# DMM-8E-2.net
KiCad netlist of a schematic drawn in EAGLE
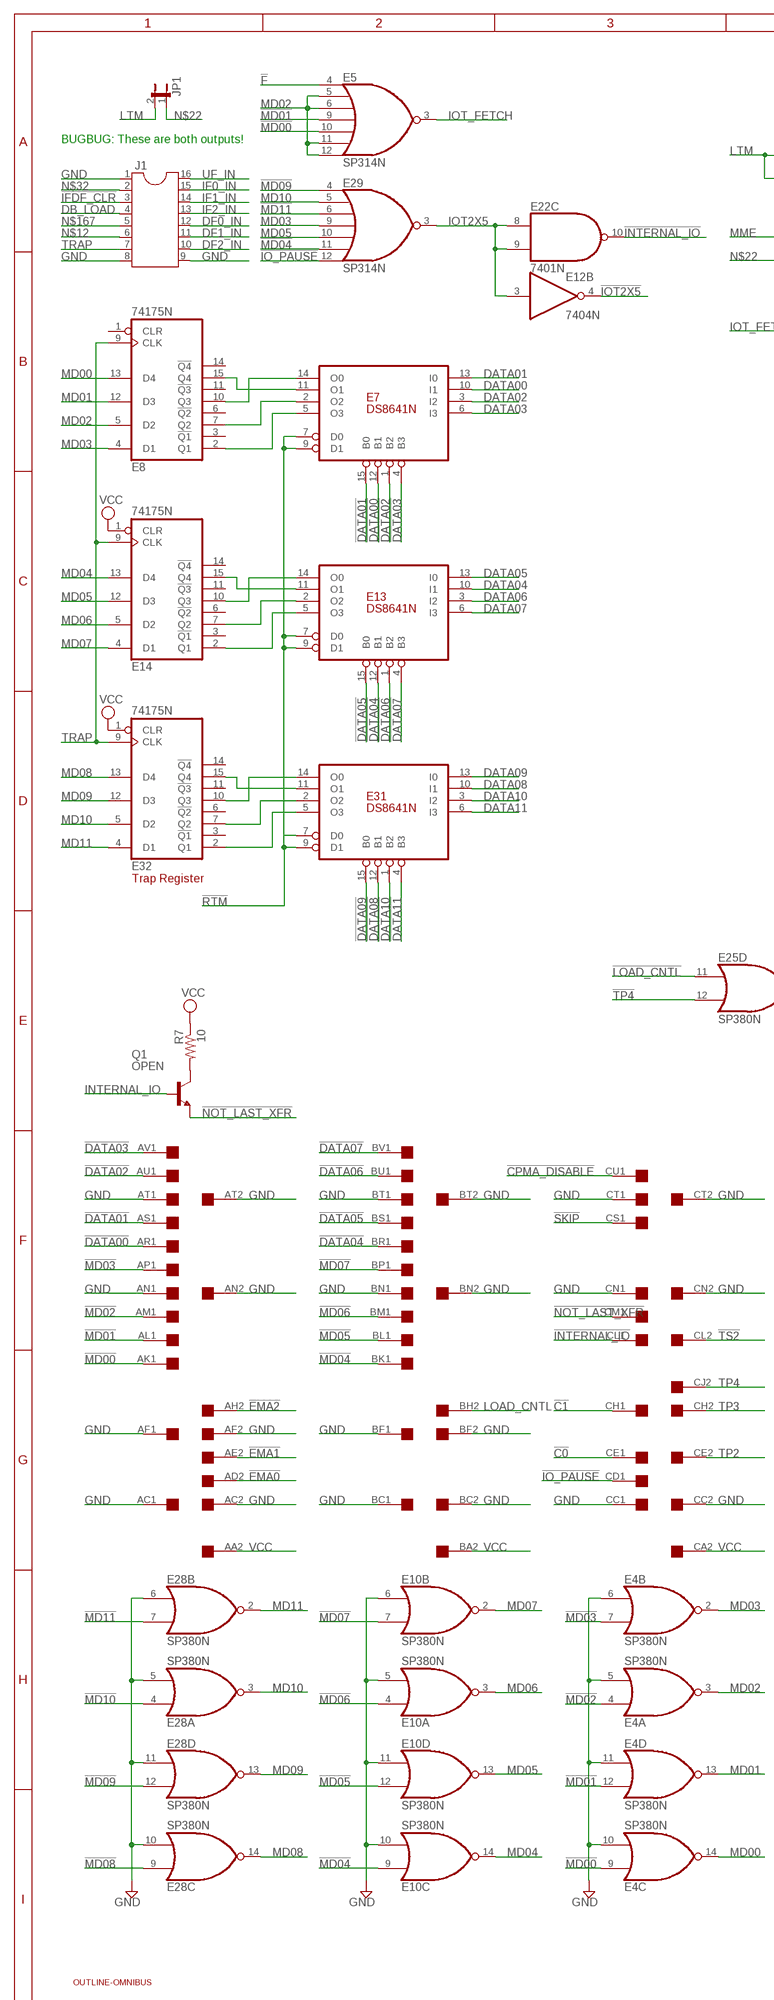
[diagram p0: schematic, sheet 1, part 1 of 2]
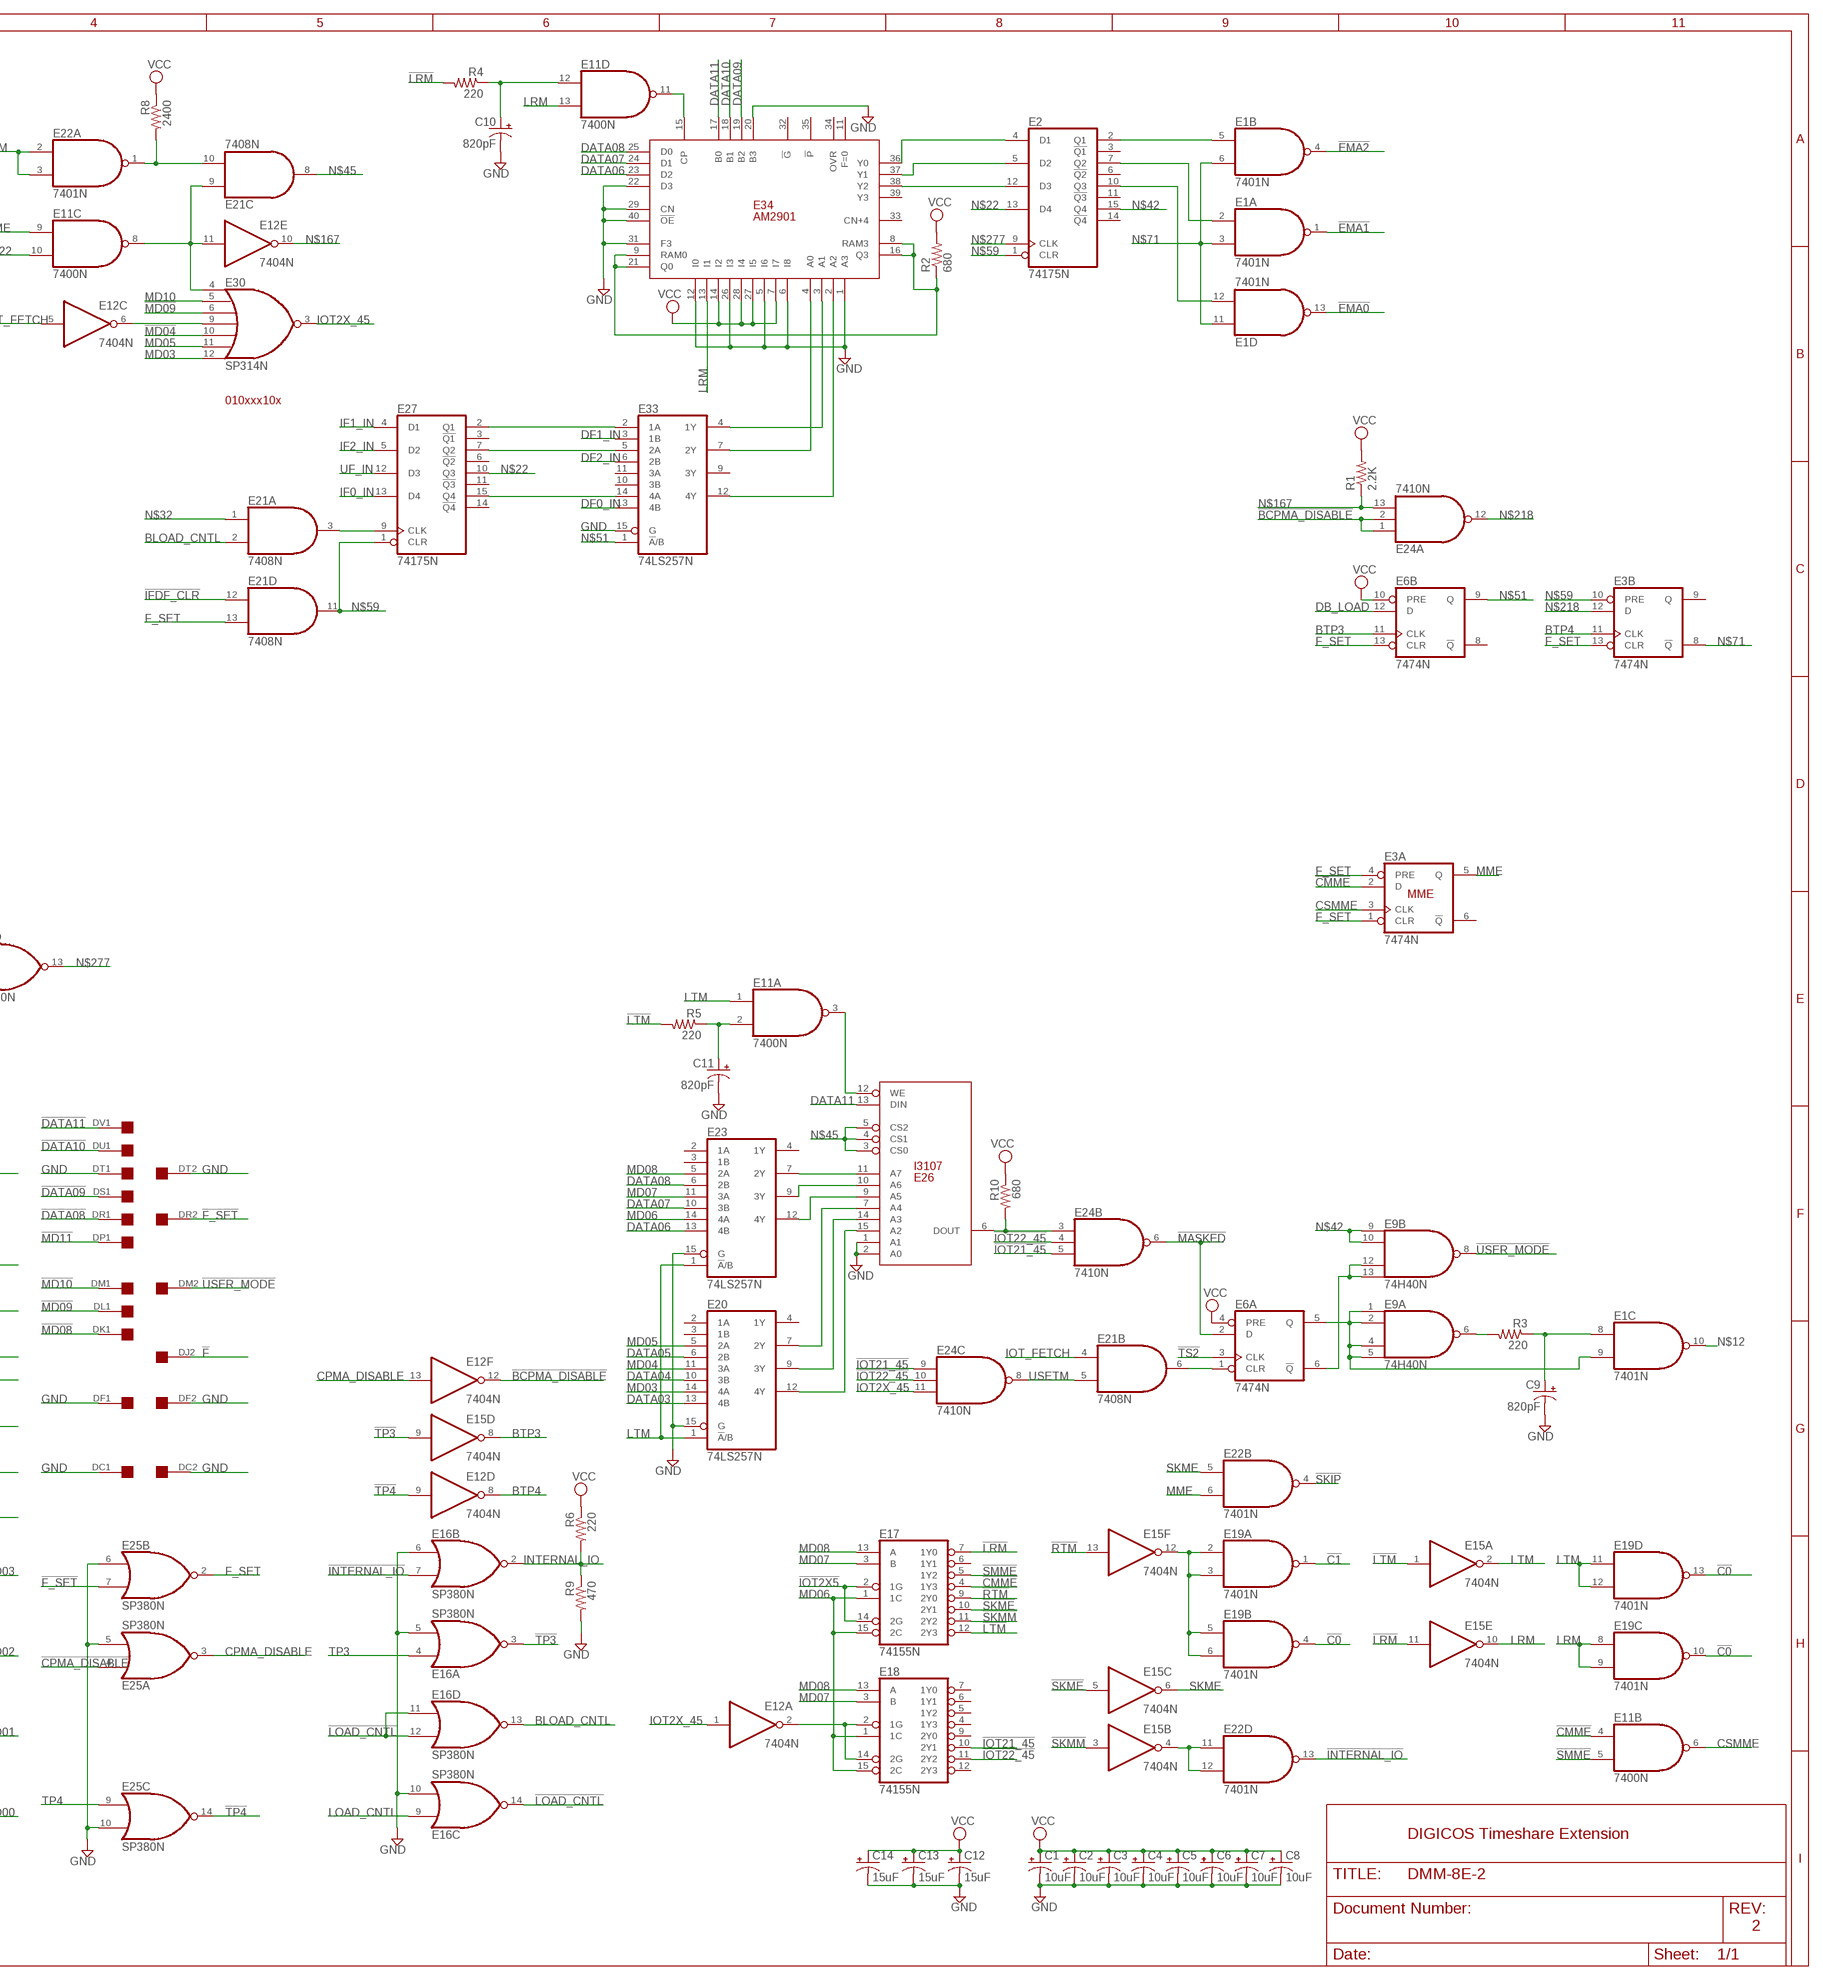
[diagram p1: schematic, sheet 1, part 2 of 2]

(export (version "E")
  (design (tool "Eeschema 10.0.6"))
  (components
    (comp (ref "C1")
      (value "10uF")
      (footprint "eagle-import:E15-5")
      (libsource (lib "eagle-import") (part "CPOL-USE15-5AXIAL"))
    )
    (comp (ref "C2")
      (value "10uF")
      (footprint "eagle-import:E15-5")
      (libsource (lib "eagle-import") (part "CPOL-USE15-5AXIAL"))
    )
    (comp (ref "C3")
      (value "10uF")
      (footprint "eagle-import:E15-5")
      (libsource (lib "eagle-import") (part "CPOL-USE15-5AXIAL"))
    )
    (comp (ref "C4")
      (value "10uF")
      (footprint "eagle-import:E15-5")
      (libsource (lib "eagle-import") (part "CPOL-USE15-5AXIAL"))
    )
    (comp (ref "C5")
      (value "10uF")
      (footprint "eagle-import:E15-5")
      (libsource (lib "eagle-import") (part "CPOL-USE15-5AXIAL"))
    )
    (comp (ref "C6")
      (value "10uF")
      (footprint "eagle-import:E15-5")
      (libsource (lib "eagle-import") (part "CPOL-USE15-5AXIAL"))
    )
    (comp (ref "C7")
      (value "10uF")
      (footprint "eagle-import:E15-5")
      (libsource (lib "eagle-import") (part "CPOL-USE15-5AXIAL"))
    )
    (comp (ref "C8")
      (value "10uF")
      (footprint "eagle-import:E15-5")
      (libsource (lib "eagle-import") (part "CPOL-USE15-5AXIAL"))
    )
    (comp (ref "C9")
      (value "820pF")
      (footprint "eagle-import:B45181C")
      (libsource (lib "eagle-import") (part "CPOL-USB45181C"))
    )
    (comp (ref "C10")
      (value "820pF")
      (footprint "eagle-import:B45181C")
      (libsource (lib "eagle-import") (part "CPOL-USB45181C"))
    )
    (comp (ref "C11")
      (value "820pF")
      (footprint "eagle-import:B45181C")
      (libsource (lib "eagle-import") (part "CPOL-USB45181C"))
    )
    (comp (ref "C12")
      (value "15uF")
      (footprint "eagle-import:TT5D7")
      (libsource (lib "eagle-import") (part "CPOL-USTT5D7"))
    )
    (comp (ref "C13")
      (value "15uF")
      (footprint "eagle-import:TT5D7")
      (libsource (lib "eagle-import") (part "CPOL-USTT5D7"))
    )
    (comp (ref "C14")
      (value "15uF")
      (footprint "eagle-import:TT5D7")
      (libsource (lib "eagle-import") (part "CPOL-USTT5D7"))
    )
    (comp (ref "E1")
      (value "7401N")
      (footprint "eagle-import:DIL14")
      (libsource (lib "eagle-import") (part "7401NLS"))
    )
    (comp (ref "E2")
      (value "74175N")
      (footprint "eagle-import:DIL16")
      (libsource (lib "eagle-import") (part "74175N"))
    )
    (comp (ref "E3")
      (value "7474N")
      (footprint "eagle-import:DIL14")
      (libsource (lib "eagle-import") (part "7474NLS"))
    )
    (comp (ref "E4")
      (value "SP380N")
      (footprint "eagle-import:DIL14")
      (libsource (lib "eagle-import") (part "SP380N"))
    )
    (comp (ref "E5")
      (value "SP314N")
      (footprint "eagle-import:DIL14")
      (libsource (lib "eagle-import") (part "SP314N"))
    )
    (comp (ref "E6")
      (value "7474N")
      (footprint "eagle-import:DIL14")
      (libsource (lib "eagle-import") (part "7474NLS"))
    )
    (comp (ref "E7")
      (value "DS8641N")
      (footprint "eagle-import:DIL16")
      (libsource (lib "eagle-import") (part "DS8641N"))
    )
    (comp (ref "E8")
      (value "74175N")
      (footprint "eagle-import:DIL16")
      (libsource (lib "eagle-import") (part "74175N"))
    )
    (comp (ref "E9")
      (value "74H40N")
      (footprint "eagle-import:DIL14")
      (libsource (lib "eagle-import") (part "7440N"))
    )
    (comp (ref "E10")
      (value "SP380N")
      (footprint "eagle-import:DIL14")
      (libsource (lib "eagle-import") (part "SP380N"))
    )
    (comp (ref "E11")
      (value "7400N")
      (footprint "eagle-import:DIL14")
      (libsource (lib "eagle-import") (part "7400N"))
    )
    (comp (ref "E12")
      (value "7404N")
      (footprint "eagle-import:DIL14")
      (libsource (lib "eagle-import") (part "7404N"))
    )
    (comp (ref "E13")
      (value "DS8641N")
      (footprint "eagle-import:DIL16")
      (libsource (lib "eagle-import") (part "DS8641N"))
    )
    (comp (ref "E14")
      (value "74175N")
      (footprint "eagle-import:DIL16")
      (libsource (lib "eagle-import") (part "74175N"))
    )
    (comp (ref "E15")
      (value "7404N")
      (footprint "eagle-import:DIL14")
      (libsource (lib "eagle-import") (part "7404N"))
    )
    (comp (ref "E16")
      (value "SP380N")
      (footprint "eagle-import:DIL14")
      (libsource (lib "eagle-import") (part "SP380N"))
    )
    (comp (ref "E17")
      (value "74155N")
      (footprint "eagle-import:DIL16")
      (libsource (lib "eagle-import") (part "74155N"))
    )
    (comp (ref "E18")
      (value "74155N")
      (footprint "eagle-import:DIL16")
      (libsource (lib "eagle-import") (part "74155N"))
    )
    (comp (ref "E19")
      (value "7401N")
      (footprint "eagle-import:DIL14")
      (libsource (lib "eagle-import") (part "7401NLS"))
    )
    (comp (ref "E20")
      (value "74LS257N")
      (footprint "eagle-import:DIL16")
      (libsource (lib "eagle-import") (part "74257NLS"))
    )
    (comp (ref "E21")
      (value "7408N")
      (footprint "eagle-import:DIL14")
      (libsource (lib "eagle-import") (part "7408NLS"))
    )
    (comp (ref "E22")
      (value "7401N")
      (footprint "eagle-import:DIL14")
      (libsource (lib "eagle-import") (part "7401NLS"))
    )
    (comp (ref "E23")
      (value "74LS257N")
      (footprint "eagle-import:DIL16")
      (libsource (lib "eagle-import") (part "74257NLS"))
    )
    (comp (ref "E24")
      (value "7410N")
      (footprint "eagle-import:DIL14")
      (libsource (lib "eagle-import") (part "7410N"))
    )
    (comp (ref "E25")
      (value "SP380N")
      (footprint "eagle-import:DIL14")
      (libsource (lib "eagle-import") (part "SP380N"))
    )
    (comp (ref "E26")
      (value "I3107")
      (footprint "eagle-import:DIL16")
      (libsource (lib "eagle-import") (part "I3107"))
    )
    (comp (ref "E27")
      (value "74175N")
      (footprint "eagle-import:DIL16")
      (libsource (lib "eagle-import") (part "74175N"))
    )
    (comp (ref "E28")
      (value "SP380N")
      (footprint "eagle-import:DIL14")
      (libsource (lib "eagle-import") (part "SP380N"))
    )
    (comp (ref "E29")
      (value "SP314N")
      (footprint "eagle-import:DIL14")
      (libsource (lib "eagle-import") (part "SP314N"))
    )
    (comp (ref "E30")
      (value "SP314N")
      (footprint "eagle-import:DIL14")
      (libsource (lib "eagle-import") (part "SP314N"))
    )
    (comp (ref "E31")
      (value "DS8641N")
      (footprint "eagle-import:DIL16")
      (libsource (lib "eagle-import") (part "DS8641N"))
    )
    (comp (ref "E32")
      (value "74175N")
      (footprint "eagle-import:DIL16")
      (libsource (lib "eagle-import") (part "74175N"))
    )
    (comp (ref "E33")
      (value "74LS257N")
      (footprint "eagle-import:DIL16")
      (libsource (lib "eagle-import") (part "74257NLS"))
    )
    (comp (ref "E34")
      (value "AM2901")
      (footprint "eagle-import:DIL40")
      (libsource (lib "eagle-import") (part "AM2901"))
    )
    (comp (ref "J1")
      (value "DIL16S")
      (footprint "eagle-import:SOCKET-16")
      (libsource (lib "eagle-import") (part "DIL16S"))
    )
    (comp (ref "JP1")
      (value "JP1E")
      (footprint "eagle-import:JP1")
      (libsource (lib "eagle-import") (part "JP1E"))
    )
    (comp (ref "Q1")
      (value "OPEN")
      (footprint "eagle-import:TO5")
      (libsource (lib "eagle-import") (part "-NPN-TO5"))
    )
    (comp (ref "R1")
      (value "2.2K")
      (footprint "eagle-import:0207_10")
      (libsource (lib "eagle-import") (part "R-US_0207/10"))
    )
    (comp (ref "R2")
      (value "680")
      (footprint "eagle-import:0207_10")
      (libsource (lib "eagle-import") (part "R-US_0207/10"))
    )
    (comp (ref "R3")
      (value "220")
      (footprint "eagle-import:0207_10")
      (libsource (lib "eagle-import") (part "R-US_0207/10"))
    )
    (comp (ref "R4")
      (value "220")
      (footprint "eagle-import:0207_10")
      (libsource (lib "eagle-import") (part "R-US_0207/10"))
    )
    (comp (ref "R5")
      (value "220")
      (footprint "eagle-import:0207_10")
      (libsource (lib "eagle-import") (part "R-US_0207/10"))
    )
    (comp (ref "R6")
      (value "220")
      (footprint "eagle-import:0207_10")
      (libsource (lib "eagle-import") (part "R-US_0207/10"))
    )
    (comp (ref "R7")
      (value "10")
      (footprint "eagle-import:0207_10")
      (libsource (lib "eagle-import") (part "R-US_0207/10"))
    )
    (comp (ref "R8")
      (value "2400")
      (footprint "eagle-import:0207_10")
      (libsource (lib "eagle-import") (part "R-US_0207/10"))
    )
    (comp (ref "R9")
      (value "470")
      (footprint "eagle-import:0207_10")
      (libsource (lib "eagle-import") (part "R-US_0207/10"))
    )
    (comp (ref "R10")
      (value "680")
      (footprint "eagle-import:0207_10")
      (libsource (lib "eagle-import") (part "R-US_0207/10"))
    )
    (comp (ref "U$1")
      (value "OUTLINE-OMNIBUS")
      (footprint "eagle-import:OMNIBUS")
      (libsource (lib "eagle-import") (part "OUTLINE-OMNIBUS"))
    )
    (comp (ref "U$2")
      (value "QUAD")
      (footprint "eagle-import:EDGE-CON8")
      (libsource (lib "eagle-import") (part "QUAD"))
    )
  )
  (nets
    (net (code "1") (name "/BLOAD_CNTL") (class "Default")
      (node (ref "E16") (pin "13") (pinfunction "O_13") (pintype "output"))
      (node (ref "E21") (pin "2") (pinfunction "I1_2") (pintype "input"))
    )
    (net (code "2") (name "/BTP3") (class "Default")
      (node (ref "E15") (pin "8") (pinfunction "O_8") (pintype "output"))
      (node (ref "E6") (pin "11") (pinfunction "CLK_11") (pintype "input"))
    )
    (net (code "3") (name "/BTP4") (class "Default")
      (node (ref "E12") (pin "8") (pinfunction "O_8") (pintype "output"))
      (node (ref "E3") (pin "11") (pinfunction "CLK_11") (pintype "input"))
    )
    (net (code "4") (name "/CPMA_DISABLE") (class "Default")
      (node (ref "E12") (pin "13") (pinfunction "I_13") (pintype "input"))
      (node (ref "E25") (pin "3") (pinfunction "O_3") (pintype "output"))
    )
    (net (code "5") (name "/CSMME") (class "Default")
      (node (ref "E11") (pin "6") (pinfunction "O_6") (pintype "output"))
      (node (ref "E3") (pin "3") (pinfunction "CLK_3") (pintype "input"))
    )
    (net (code "6") (name "/DATA00") (class "Default")
      (node (ref "E7") (pin "10") (pinfunction "I1_10") (pintype "output"))
    )
    (net (code "7") (name "/DATA01") (class "Default")
      (node (ref "E7") (pin "13") (pinfunction "I0_13") (pintype "output"))
    )
    (net (code "8") (name "/DATA02") (class "Default")
      (node (ref "E7") (pin "3") (pinfunction "I2_3") (pintype "output"))
    )
    (net (code "9") (name "/DATA03") (class "Default")
      (node (ref "E20") (pin "13") (pinfunction "4B_13") (pintype "input"))
      (node (ref "E7") (pin "6") (pinfunction "I3_6") (pintype "output"))
    )
    (net (code "10") (name "/DATA04") (class "Default")
      (node (ref "E13") (pin "10") (pinfunction "I1_10") (pintype "output"))
      (node (ref "E20") (pin "10") (pinfunction "3B_10") (pintype "input"))
    )
    (net (code "11") (name "/DATA05") (class "Default")
      (node (ref "E13") (pin "13") (pinfunction "I0_13") (pintype "output"))
      (node (ref "E20") (pin "6") (pinfunction "2B_6") (pintype "input"))
    )
    (net (code "12") (name "/DATA06") (class "Default")
      (node (ref "E13") (pin "3") (pinfunction "I2_3") (pintype "output"))
      (node (ref "E23") (pin "13") (pinfunction "4B_13") (pintype "input"))
      (node (ref "E34") (pin "23") (pinfunction "D2_23") (pintype "input"))
    )
    (net (code "13") (name "/DATA07") (class "Default")
      (node (ref "E13") (pin "6") (pinfunction "I3_6") (pintype "output"))
      (node (ref "E23") (pin "10") (pinfunction "3B_10") (pintype "input"))
      (node (ref "E34") (pin "24") (pinfunction "D1_24") (pintype "input"))
    )
    (net (code "14") (name "/DATA08") (class "Default")
      (node (ref "E23") (pin "6") (pinfunction "2B_6") (pintype "input"))
      (node (ref "E31") (pin "10") (pinfunction "I1_10") (pintype "output"))
      (node (ref "E34") (pin "25") (pinfunction "D0_25") (pintype "input"))
    )
    (net (code "15") (name "/DATA09") (class "Default")
      (node (ref "E31") (pin "13") (pinfunction "I0_13") (pintype "output"))
      (node (ref "E34") (pin "19") (pinfunction "B2_19") (pintype "input"))
    )
    (net (code "16") (name "/DATA10") (class "Default")
      (node (ref "E31") (pin "3") (pinfunction "I2_3") (pintype "output"))
      (node (ref "E34") (pin "18") (pinfunction "B1_18") (pintype "input"))
    )
    (net (code "17") (name "/DATA11") (class "Default")
      (node (ref "E26") (pin "13") (pinfunction "DIN_13") (pintype "input"))
      (node (ref "E31") (pin "6") (pinfunction "I3_6") (pintype "output"))
      (node (ref "E34") (pin "17") (pinfunction "B0_17") (pintype "input"))
    )
    (net (code "18") (name "/DB_LOAD") (class "Default")
      (node (ref "E6") (pin "12") (pinfunction "D_12") (pintype "input"))
      (node (ref "J1") (pin "4") (pinfunction "4_4") (pintype "passive"))
    )
    (net (code "19") (name "/DF0_IN") (class "Default")
      (node (ref "E33") (pin "13") (pinfunction "4B_13") (pintype "input"))
      (node (ref "J1") (pin "12") (pinfunction "12_12") (pintype "passive"))
    )
    (net (code "20") (name "/DF1_IN") (class "Default")
      (node (ref "E33") (pin "3") (pinfunction "1B_3") (pintype "input"))
      (node (ref "J1") (pin "11") (pinfunction "11_11") (pintype "passive"))
    )
    (net (code "21") (name "/DF2_IN") (class "Default")
      (node (ref "E33") (pin "6") (pinfunction "2B_6") (pintype "input"))
      (node (ref "J1") (pin "10") (pinfunction "10_10") (pintype "passive"))
    )
    (net (code "22") (name "/F_SET") (class "Default")
      (node (ref "E21") (pin "13") (pinfunction "I1_13") (pintype "input"))
      (node (ref "E25") (pin "2") (pinfunction "O_2") (pintype "output"))
      (node (ref "E3") (pin "1") (pinfunction "CLR_1") (pintype "input"))
      (node (ref "E3") (pin "13") (pinfunction "CLR_13") (pintype "input"))
      (node (ref "E3") (pin "4") (pinfunction "PRE_4") (pintype "input"))
      (node (ref "E6") (pin "13") (pinfunction "CLR_13") (pintype "input"))
    )
    (net (code "23") (name "/IF0_IN") (class "Default")
      (node (ref "E27") (pin "13") (pinfunction "D4_13") (pintype "input"))
      (node (ref "J1") (pin "15") (pinfunction "15_15") (pintype "passive"))
    )
    (net (code "24") (name "/IF1_IN") (class "Default")
      (node (ref "E27") (pin "4") (pinfunction "D1_4") (pintype "input"))
      (node (ref "J1") (pin "14") (pinfunction "14_14") (pintype "passive"))
    )
    (net (code "25") (name "/IF2_IN") (class "Default")
      (node (ref "E27") (pin "5") (pinfunction "D2_5") (pintype "input"))
      (node (ref "J1") (pin "13") (pinfunction "13_13") (pintype "passive"))
    )
    (net (code "26") (name "/INTERNAL_IO") (class "Default")
      (node (ref "E16") (pin "2") (pinfunction "O_2") (pintype "output"))
      (node (ref "Q1") (pin "2") (pinfunction "B_2") (pintype "passive"))
      (node (ref "R6") (pin "2") (pinfunction "2_2") (pintype "passive"))
      (node (ref "R9") (pin "1") (pinfunction "1_1") (pintype "passive"))
    )
    (net (code "27") (name "/IOT2X5") (class "Default")
      (node (ref "E12") (pin "3") (pinfunction "I_3") (pintype "input"))
      (node (ref "E22") (pin "8") (pinfunction "I0_8") (pintype "input"))
      (node (ref "E22") (pin "9") (pinfunction "I1_9") (pintype "input"))
      (node (ref "E29") (pin "3") (pinfunction "O_3") (pintype "output"))
    )
    (net (code "28") (name "/IOT2X_45") (class "Default")
      (node (ref "E12") (pin "1") (pinfunction "I_1") (pintype "input"))
      (node (ref "E24") (pin "11") (pinfunction "I2_11") (pintype "input"))
      (node (ref "E30") (pin "3") (pinfunction "O_3") (pintype "output"))
    )
    (net (code "29") (name "/IOT_FETCH") (class "Default")
      (node (ref "E12") (pin "5") (pinfunction "I_5") (pintype "input"))
      (node (ref "E21") (pin "4") (pinfunction "I0_4") (pintype "input"))
      (node (ref "E5") (pin "3") (pinfunction "O_3") (pintype "output"))
    )
    (net (code "30") (name "/LOAD_CNTL") (class "Default")
      (node (ref "E16") (pin "9") (pinfunction "I0_9") (pintype "input"))
      (node (ref "U$2") (pin "BH2") (pinfunction "1_BH2") (pintype "bidirectional"))
    )
    (net (code "31") (name "/LRM") (class "Default")
      (node (ref "E11") (pin "13") (pinfunction "I1_13") (pintype "input"))
      (node (ref "E15") (pin "10") (pinfunction "O_10") (pintype "output"))
      (node (ref "E19") (pin "8") (pinfunction "I0_8") (pintype "input"))
      (node (ref "E19") (pin "9") (pinfunction "I1_9") (pintype "input"))
      (node (ref "E34") (pin "13") (pinfunction "I1_13") (pintype "input"))
    )
    (net (code "32") (name "/LTM") (class "Default")
      (node (ref "E11") (pin "1") (pinfunction "I0_1") (pintype "input"))
      (node (ref "E15") (pin "2") (pinfunction "O_2") (pintype "output"))
      (node (ref "E19") (pin "11") (pinfunction "I0_11") (pintype "input"))
      (node (ref "E19") (pin "12") (pinfunction "I1_12") (pintype "input"))
      (node (ref "E20") (pin "1") (pinfunction "~{A}/B_1") (pintype "input"))
      (node (ref "E22") (pin "2") (pinfunction "I0_2") (pintype "input"))
      (node (ref "E22") (pin "3") (pinfunction "I1_3") (pintype "input"))
      (node (ref "E23") (pin "1") (pinfunction "~{A}/B_1") (pintype "input"))
      (node (ref "JP1") (pin "2") (pinfunction "2_2") (pintype "passive"))
    )
    (net (code "33") (name "/MD00") (class "Default")
      (node (ref "E4") (pin "14") (pinfunction "O_14") (pintype "output"))
      (node (ref "E8") (pin "13") (pinfunction "D4_13") (pintype "input"))
    )
    (net (code "34") (name "/MD01") (class "Default")
      (node (ref "E4") (pin "13") (pinfunction "O_13") (pintype "output"))
      (node (ref "E8") (pin "12") (pinfunction "D3_12") (pintype "input"))
    )
    (net (code "35") (name "/MD02") (class "Default")
      (node (ref "E4") (pin "3") (pinfunction "O_3") (pintype "output"))
      (node (ref "E5") (pin "11") (pinfunction "I5_11") (pintype "input"))
      (node (ref "E5") (pin "12") (pinfunction "I6_12") (pintype "input"))
      (node (ref "E5") (pin "5") (pinfunction "I1_5") (pintype "input"))
      (node (ref "E5") (pin "6") (pinfunction "I2_6") (pintype "input"))
      (node (ref "E8") (pin "5") (pinfunction "D2_5") (pintype "input"))
    )
    (net (code "36") (name "/MD03") (class "Default")
      (node (ref "E20") (pin "14") (pinfunction "4A_14") (pintype "input"))
      (node (ref "E29") (pin "9") (pinfunction "I3_9") (pintype "input"))
      (node (ref "E30") (pin "12") (pinfunction "I6_12") (pintype "input"))
      (node (ref "E4") (pin "2") (pinfunction "O_2") (pintype "output"))
      (node (ref "E8") (pin "4") (pinfunction "D1_4") (pintype "input"))
    )
    (net (code "37") (name "/MD04") (class "Default")
      (node (ref "E10") (pin "14") (pinfunction "O_14") (pintype "output"))
      (node (ref "E14") (pin "13") (pinfunction "D4_13") (pintype "input"))
      (node (ref "E20") (pin "11") (pinfunction "3A_11") (pintype "input"))
    )
    (net (code "38") (name "/MD05") (class "Default")
      (node (ref "E10") (pin "13") (pinfunction "O_13") (pintype "output"))
      (node (ref "E14") (pin "12") (pinfunction "D3_12") (pintype "input"))
      (node (ref "E20") (pin "5") (pinfunction "2A_5") (pintype "input"))
      (node (ref "E29") (pin "10") (pinfunction "I4_10") (pintype "input"))
      (node (ref "E30") (pin "11") (pinfunction "I5_11") (pintype "input"))
    )
    (net (code "39") (name "/MD06") (class "Default")
      (node (ref "E10") (pin "3") (pinfunction "O_3") (pintype "output"))
      (node (ref "E14") (pin "5") (pinfunction "D2_5") (pintype "input"))
      (node (ref "E17") (pin "1") (pinfunction "1C_1") (pintype "input"))
      (node (ref "E17") (pin "15") (pinfunction "2C_15") (pintype "input"))
      (node (ref "E18") (pin "1") (pinfunction "1C_1") (pintype "input"))
      (node (ref "E18") (pin "15") (pinfunction "2C_15") (pintype "input"))
      (node (ref "E23") (pin "14") (pinfunction "4A_14") (pintype "input"))
    )
    (net (code "40") (name "/MD07") (class "Default")
      (node (ref "E10") (pin "2") (pinfunction "O_2") (pintype "output"))
      (node (ref "E14") (pin "4") (pinfunction "D1_4") (pintype "input"))
      (node (ref "E17") (pin "3") (pinfunction "B_3") (pintype "input"))
      (node (ref "E18") (pin "3") (pinfunction "B_3") (pintype "input"))
      (node (ref "E23") (pin "11") (pinfunction "3A_11") (pintype "input"))
    )
    (net (code "41") (name "/MD08") (class "Default")
      (node (ref "E17") (pin "13") (pinfunction "A_13") (pintype "input"))
      (node (ref "E18") (pin "13") (pinfunction "A_13") (pintype "input"))
      (node (ref "E23") (pin "5") (pinfunction "2A_5") (pintype "input"))
      (node (ref "E28") (pin "14") (pinfunction "O_14") (pintype "output"))
      (node (ref "E32") (pin "13") (pinfunction "D4_13") (pintype "input"))
    )
    (net (code "42") (name "/MD09") (class "Default")
      (node (ref "E28") (pin "13") (pinfunction "O_13") (pintype "output"))
      (node (ref "E32") (pin "12") (pinfunction "D3_12") (pintype "input"))
    )
    (net (code "43") (name "/MD10") (class "Default")
      (node (ref "E28") (pin "3") (pinfunction "O_3") (pintype "output"))
      (node (ref "E29") (pin "5") (pinfunction "I1_5") (pintype "input"))
      (node (ref "E30") (pin "5") (pinfunction "I1_5") (pintype "input"))
      (node (ref "E32") (pin "5") (pinfunction "D2_5") (pintype "input"))
    )
    (net (code "44") (name "/MD11") (class "Default")
      (node (ref "E28") (pin "2") (pinfunction "O_2") (pintype "output"))
      (node (ref "E32") (pin "4") (pinfunction "D1_4") (pintype "input"))
    )
    (net (code "45") (name "/MME") (class "Default")
      (node (ref "E11") (pin "9") (pinfunction "I0_9") (pintype "input"))
      (node (ref "E22") (pin "6") (pinfunction "I1_6") (pintype "input"))
      (node (ref "E3") (pin "5") (pinfunction "Q_5") (pintype "output"))
    )
    (net (code "46") (name "/N$12") (class "Default")
      (node (ref "E1") (pin "10") (pinfunction "O_10") (pintype "open_collector"))
      (node (ref "J1") (pin "6") (pinfunction "6_6") (pintype "passive"))
    )
    (net (code "47") (name "/N$22") (class "Default")
      (node (ref "E11") (pin "10") (pinfunction "I1_10") (pintype "input"))
      (node (ref "E2") (pin "13") (pinfunction "D4_13") (pintype "input"))
      (node (ref "E27") (pin "10") (pinfunction "Q3_10") (pintype "output"))
      (node (ref "JP1") (pin "1") (pinfunction "1_1") (pintype "passive"))
    )
    (net (code "48") (name "/N$32") (class "Default")
      (node (ref "E21") (pin "1") (pinfunction "I0_1") (pintype "input"))
      (node (ref "J1") (pin "2") (pinfunction "2_2") (pintype "passive"))
    )
    (net (code "49") (name "/N$42") (class "Default")
      (node (ref "E2") (pin "15") (pinfunction "Q4_15") (pintype "output"))
      (node (ref "E9") (pin "10") (pinfunction "I1_10") (pintype "input"))
      (node (ref "E9") (pin "9") (pinfunction "I0_9") (pintype "input"))
    )
    (net (code "50") (name "/N$45") (class "Default")
      (node (ref "E21") (pin "8") (pinfunction "O_8") (pintype "output"))
      (node (ref "E26") (pin "3") (pinfunction "CS0_3") (pintype "input"))
      (node (ref "E26") (pin "4") (pinfunction "CS1_4") (pintype "input"))
      (node (ref "E26") (pin "5") (pinfunction "CS2_5") (pintype "input"))
    )
    (net (code "51") (name "/N$51") (class "Default")
      (node (ref "E33") (pin "1") (pinfunction "~{A}/B_1") (pintype "input"))
      (node (ref "E6") (pin "9") (pinfunction "Q_9") (pintype "output"))
    )
    (net (code "52") (name "/N$59") (class "Default")
      (node (ref "E2") (pin "1") (pinfunction "CLR_1") (pintype "input"))
      (node (ref "E21") (pin "11") (pinfunction "O_11") (pintype "output"))
      (node (ref "E27") (pin "1") (pinfunction "CLR_1") (pintype "input"))
      (node (ref "E3") (pin "10") (pinfunction "PRE_10") (pintype "input"))
    )
    (net (code "53") (name "/N$71") (class "Default")
      (node (ref "E1") (pin "11") (pinfunction "I0_11") (pintype "input"))
      (node (ref "E1") (pin "3") (pinfunction "I1_3") (pintype "input"))
      (node (ref "E1") (pin "6") (pinfunction "I1_6") (pintype "input"))
      (node (ref "E3") (pin "8") (pinfunction "~{Q}_8") (pintype "output"))
    )
    (net (code "54") (name "/N$167") (class "Default")
      (node (ref "E12") (pin "10") (pinfunction "O_10") (pintype "output"))
      (node (ref "E24") (pin "13") (pinfunction "I2_13") (pintype "input"))
      (node (ref "J1") (pin "5") (pinfunction "5_5") (pintype "passive"))
      (node (ref "R1") (pin "1") (pinfunction "1_1") (pintype "passive"))
    )
    (net (code "55") (name "/N$218") (class "Default")
      (node (ref "E24") (pin "12") (pinfunction "O_12") (pintype "output"))
      (node (ref "E3") (pin "12") (pinfunction "D_12") (pintype "input"))
    )
    (net (code "56") (name "/N$277") (class "Default")
      (node (ref "E2") (pin "9") (pinfunction "CLK_9") (pintype "input"))
      (node (ref "E25") (pin "13") (pinfunction "O_13") (pintype "output"))
    )
    (net (code "57") (name "/SKME") (class "Default")
      (node (ref "E15") (pin "6") (pinfunction "O_6") (pintype "output"))
      (node (ref "E22") (pin "5") (pinfunction "I0_5") (pintype "input"))
    )
    (net (code "58") (name "/TP2") (class "Default")
      (node (ref "U$2") (pin "CE2") (pinfunction "1_CE2") (pintype "bidirectional"))
    )
    (net (code "59") (name "/TP3") (class "Default")
      (node (ref "E16") (pin "4") (pinfunction "I0_4") (pintype "input"))
      (node (ref "U$2") (pin "CH2") (pinfunction "1_CH2") (pintype "bidirectional"))
    )
    (net (code "60") (name "/TP4") (class "Default")
      (node (ref "E25") (pin "9") (pinfunction "I0_9") (pintype "input"))
      (node (ref "U$2") (pin "CJ2") (pinfunction "1_CJ2") (pintype "bidirectional"))
    )
    (net (code "61") (name "/TRAP") (class "Default")
      (node (ref "E14") (pin "9") (pinfunction "CLK_9") (pintype "input"))
      (node (ref "E32") (pin "9") (pinfunction "CLK_9") (pintype "input"))
      (node (ref "E8") (pin "9") (pinfunction "CLK_9") (pintype "input"))
      (node (ref "J1") (pin "7") (pinfunction "7_7") (pintype "passive"))
    )
    (net (code "62") (name "/UF_IN") (class "Default")
      (node (ref "E27") (pin "12") (pinfunction "D3_12") (pintype "input"))
      (node (ref "J1") (pin "16") (pinfunction "16_16") (pintype "passive"))
    )
    (net (code "63") (name "/USETM") (class "Default")
      (node (ref "E21") (pin "5") (pinfunction "I1_5") (pintype "input"))
      (node (ref "E24") (pin "8") (pinfunction "O_8") (pintype "output"))
    )
    (net (code "64") (name "/~{BCPMA_DISABLE}") (class "Default")
      (node (ref "E12") (pin "12") (pinfunction "O_12") (pintype "output"))
      (node (ref "E24") (pin "1") (pinfunction "I0_1") (pintype "input"))
      (node (ref "E24") (pin "2") (pinfunction "I1_2") (pintype "input"))
    )
    (net (code "65") (name "/~{C0}") (class "Default")
      (node (ref "E19") (pin "10") (pinfunction "O_10") (pintype "open_collector"))
      (node (ref "E19") (pin "13") (pinfunction "O_13") (pintype "open_collector"))
      (node (ref "E19") (pin "4") (pinfunction "O_4") (pintype "open_collector"))
      (node (ref "U$2") (pin "CE1") (pinfunction "1_CE1") (pintype "bidirectional"))
    )
    (net (code "66") (name "/~{C1}") (class "Default")
      (node (ref "E19") (pin "1") (pinfunction "O_1") (pintype "open_collector"))
      (node (ref "U$2") (pin "CH1") (pinfunction "1_CH1") (pintype "bidirectional"))
    )
    (net (code "67") (name "/~{CMME}") (class "Default")
      (node (ref "E11") (pin "4") (pinfunction "I0_4") (pintype "input"))
      (node (ref "E17") (pin "4") (pinfunction "1Y3_4") (pintype "output"))
      (node (ref "E3") (pin "2") (pinfunction "D_2") (pintype "input"))
    )
    (net (code "68") (name "/~{CPMA_DISABLE}") (class "Default")
      (node (ref "E25") (pin "4") (pinfunction "I0_4") (pintype "input"))
      (node (ref "U$2") (pin "CU1") (pinfunction "1_CU1") (pintype "bidirectional"))
    )
    (net (code "69") (name "/~{DATA00}") (class "Default")
      (node (ref "E7") (pin "12") (pinfunction "B1_12") (pintype "bidirectional"))
      (node (ref "U$2") (pin "AR1") (pinfunction "1_AR1") (pintype "bidirectional"))
    )
    (net (code "70") (name "/~{DATA01}") (class "Default")
      (node (ref "E7") (pin "15") (pinfunction "B0_15") (pintype "bidirectional"))
      (node (ref "U$2") (pin "AS1") (pinfunction "1_AS1") (pintype "bidirectional"))
    )
    (net (code "71") (name "/~{DATA02}") (class "Default")
      (node (ref "E7") (pin "1") (pinfunction "B2_1") (pintype "bidirectional"))
      (node (ref "U$2") (pin "AU1") (pinfunction "1_AU1") (pintype "bidirectional"))
    )
    (net (code "72") (name "/~{DATA03}") (class "Default")
      (node (ref "E7") (pin "4") (pinfunction "B3_4") (pintype "bidirectional"))
      (node (ref "U$2") (pin "AV1") (pinfunction "1_AV1") (pintype "bidirectional"))
    )
    (net (code "73") (name "/~{DATA04}") (class "Default")
      (node (ref "E13") (pin "12") (pinfunction "B1_12") (pintype "bidirectional"))
      (node (ref "U$2") (pin "BR1") (pinfunction "1_BR1") (pintype "bidirectional"))
    )
    (net (code "74") (name "/~{DATA05}") (class "Default")
      (node (ref "E13") (pin "15") (pinfunction "B0_15") (pintype "bidirectional"))
      (node (ref "U$2") (pin "BS1") (pinfunction "1_BS1") (pintype "bidirectional"))
    )
    (net (code "75") (name "/~{DATA06}") (class "Default")
      (node (ref "E13") (pin "1") (pinfunction "B2_1") (pintype "bidirectional"))
      (node (ref "U$2") (pin "BU1") (pinfunction "1_BU1") (pintype "bidirectional"))
    )
    (net (code "76") (name "/~{DATA07}") (class "Default")
      (node (ref "E13") (pin "4") (pinfunction "B3_4") (pintype "bidirectional"))
      (node (ref "U$2") (pin "BV1") (pinfunction "1_BV1") (pintype "bidirectional"))
    )
    (net (code "77") (name "/~{DATA08}") (class "Default")
      (node (ref "E31") (pin "12") (pinfunction "B1_12") (pintype "bidirectional"))
      (node (ref "U$2") (pin "DR1") (pinfunction "1_DR1") (pintype "bidirectional"))
    )
    (net (code "78") (name "/~{DATA09}") (class "Default")
      (node (ref "E31") (pin "15") (pinfunction "B0_15") (pintype "bidirectional"))
      (node (ref "U$2") (pin "DS1") (pinfunction "1_DS1") (pintype "bidirectional"))
    )
    (net (code "79") (name "/~{DATA10}") (class "Default")
      (node (ref "E31") (pin "1") (pinfunction "B2_1") (pintype "bidirectional"))
      (node (ref "U$2") (pin "DU1") (pinfunction "1_DU1") (pintype "bidirectional"))
    )
    (net (code "80") (name "/~{DATA11}") (class "Default")
      (node (ref "E31") (pin "4") (pinfunction "B3_4") (pintype "bidirectional"))
      (node (ref "U$2") (pin "DV1") (pinfunction "1_DV1") (pintype "bidirectional"))
    )
    (net (code "81") (name "/~{EMA0}") (class "Default")
      (node (ref "E1") (pin "13") (pinfunction "O_13") (pintype "open_collector"))
      (node (ref "U$2") (pin "AD2") (pinfunction "1_AD2") (pintype "bidirectional"))
    )
    (net (code "82") (name "/~{EMA1}") (class "Default")
      (node (ref "E1") (pin "1") (pinfunction "O_1") (pintype "open_collector"))
      (node (ref "U$2") (pin "AE2") (pinfunction "1_AE2") (pintype "bidirectional"))
    )
    (net (code "83") (name "/~{EMA2}") (class "Default")
      (node (ref "E1") (pin "4") (pinfunction "O_4") (pintype "open_collector"))
      (node (ref "U$2") (pin "AH2") (pinfunction "1_AH2") (pintype "bidirectional"))
    )
    (net (code "84") (name "/~{F_SET}") (class "Default")
      (node (ref "E25") (pin "7") (pinfunction "I1_7") (pintype "input"))
      (node (ref "U$2") (pin "DR2") (pinfunction "1_DR2") (pintype "bidirectional"))
    )
    (net (code "85") (name "/~{F}") (class "Default")
      (node (ref "E5") (pin "4") (pinfunction "I0_4") (pintype "input"))
      (node (ref "U$2") (pin "DJ2") (pinfunction "1_DJ2") (pintype "bidirectional"))
    )
    (net (code "86") (name "/~{IFDF_CLR}") (class "Default")
      (node (ref "E21") (pin "12") (pinfunction "I0_12") (pintype "input"))
      (node (ref "J1") (pin "3") (pinfunction "3_3") (pintype "passive"))
    )
    (net (code "87") (name "/~{INTERNAL_IO}") (class "Default")
      (node (ref "E16") (pin "7") (pinfunction "I1_7") (pintype "input"))
      (node (ref "E22") (pin "10") (pinfunction "O_10") (pintype "open_collector"))
      (node (ref "E22") (pin "13") (pinfunction "O_13") (pintype "open_collector"))
      (node (ref "U$2") (pin "CL1") (pinfunction "1_CL1") (pintype "bidirectional"))
    )
    (net (code "88") (name "/~{IOT2X5}") (class "Default")
      (node (ref "E12") (pin "4") (pinfunction "O_4") (pintype "output"))
      (node (ref "E17") (pin "14") (pinfunction "2G_14") (pintype "input"))
      (node (ref "E17") (pin "2") (pinfunction "1G_2") (pintype "input"))
    )
    (net (code "89") (name "/~{IOT21_45}") (class "Default")
      (node (ref "E18") (pin "10") (pinfunction "2Y1_10") (pintype "output"))
      (node (ref "E24") (pin "5") (pinfunction "I2_5") (pintype "input"))
      (node (ref "E24") (pin "9") (pinfunction "I0_9") (pintype "input"))
    )
    (net (code "90") (name "/~{IOT22_45}") (class "Default")
      (node (ref "E18") (pin "11") (pinfunction "2Y2_11") (pintype "output"))
      (node (ref "E24") (pin "10") (pinfunction "I1_10") (pintype "input"))
      (node (ref "E24") (pin "4") (pinfunction "I1_4") (pintype "input"))
    )
    (net (code "91") (name "/~{IO_PAUSE}") (class "Default")
      (node (ref "E29") (pin "12") (pinfunction "I6_12") (pintype "input"))
      (node (ref "U$2") (pin "CD1") (pinfunction "1_CD1") (pintype "bidirectional"))
    )
    (net (code "92") (name "/~{LOAD_CNTL}") (class "Default")
      (node (ref "E16") (pin "11") (pinfunction "I0_11") (pintype "input"))
      (node (ref "E16") (pin "12") (pinfunction "I1_12") (pintype "input"))
      (node (ref "E16") (pin "14") (pinfunction "O_14") (pintype "output"))
      (node (ref "E25") (pin "11") (pinfunction "I0_11") (pintype "input"))
    )
    (net (code "93") (name "/~{LRM}") (class "Default")
      (node (ref "E15") (pin "11") (pinfunction "I_11") (pintype "input"))
      (node (ref "E17") (pin "7") (pinfunction "1Y0_7") (pintype "output"))
      (node (ref "R4") (pin "2") (pinfunction "2_2") (pintype "passive"))
    )
    (net (code "94") (name "/~{LTM}") (class "Default")
      (node (ref "E15") (pin "1") (pinfunction "I_1") (pintype "input"))
      (node (ref "E17") (pin "12") (pinfunction "2Y3_12") (pintype "output"))
      (node (ref "R5") (pin "2") (pinfunction "2_2") (pintype "passive"))
    )
    (net (code "95") (name "/~{MASKED}") (class "Default")
      (node (ref "E24") (pin "6") (pinfunction "O_6") (pintype "output"))
      (node (ref "E6") (pin "2") (pinfunction "D_2") (pintype "input"))
    )
    (net (code "96") (name "/~{MD00}") (class "Default")
      (node (ref "E4") (pin "9") (pinfunction "I0_9") (pintype "input"))
      (node (ref "E5") (pin "10") (pinfunction "I4_10") (pintype "input"))
      (node (ref "U$2") (pin "AK1") (pinfunction "1_AK1") (pintype "bidirectional"))
    )
    (net (code "97") (name "/~{MD01}") (class "Default")
      (node (ref "E4") (pin "12") (pinfunction "I1_12") (pintype "input"))
      (node (ref "E5") (pin "9") (pinfunction "I3_9") (pintype "input"))
      (node (ref "U$2") (pin "AL1") (pinfunction "1_AL1") (pintype "bidirectional"))
    )
    (net (code "98") (name "/~{MD02}") (class "Default")
      (node (ref "E4") (pin "4") (pinfunction "I0_4") (pintype "input"))
      (node (ref "U$2") (pin "AM1") (pinfunction "1_AM1") (pintype "bidirectional"))
    )
    (net (code "99") (name "/~{MD03}") (class "Default")
      (node (ref "E4") (pin "7") (pinfunction "I1_7") (pintype "input"))
      (node (ref "U$2") (pin "AP1") (pinfunction "1_AP1") (pintype "bidirectional"))
    )
    (net (code "100") (name "/~{MD04}") (class "Default")
      (node (ref "E10") (pin "9") (pinfunction "I0_9") (pintype "input"))
      (node (ref "E29") (pin "11") (pinfunction "I5_11") (pintype "input"))
      (node (ref "E30") (pin "10") (pinfunction "I4_10") (pintype "input"))
      (node (ref "U$2") (pin "BK1") (pinfunction "1_BK1") (pintype "bidirectional"))
    )
    (net (code "101") (name "/~{MD05}") (class "Default")
      (node (ref "E10") (pin "12") (pinfunction "I1_12") (pintype "input"))
      (node (ref "U$2") (pin "BL1") (pinfunction "1_BL1") (pintype "bidirectional"))
    )
    (net (code "102") (name "/~{MD06}") (class "Default")
      (node (ref "E10") (pin "4") (pinfunction "I0_4") (pintype "input"))
      (node (ref "U$2") (pin "BM1") (pinfunction "1_BM1") (pintype "bidirectional"))
    )
    (net (code "103") (name "/~{MD07}") (class "Default")
      (node (ref "E10") (pin "7") (pinfunction "I1_7") (pintype "input"))
      (node (ref "U$2") (pin "BP1") (pinfunction "1_BP1") (pintype "bidirectional"))
    )
    (net (code "104") (name "/~{MD08}") (class "Default")
      (node (ref "E28") (pin "9") (pinfunction "I0_9") (pintype "input"))
      (node (ref "U$2") (pin "DK1") (pinfunction "1_DK1") (pintype "bidirectional"))
    )
    (net (code "105") (name "/~{MD09}") (class "Default")
      (node (ref "E28") (pin "12") (pinfunction "I1_12") (pintype "input"))
      (node (ref "E29") (pin "4") (pinfunction "I0_4") (pintype "input"))
      (node (ref "E30") (pin "6") (pinfunction "I2_6") (pintype "input"))
      (node (ref "U$2") (pin "DL1") (pinfunction "1_DL1") (pintype "bidirectional"))
    )
    (net (code "106") (name "/~{MD10}") (class "Default")
      (node (ref "E28") (pin "4") (pinfunction "I0_4") (pintype "input"))
      (node (ref "U$2") (pin "DM1") (pinfunction "1_DM1") (pintype "bidirectional"))
    )
    (net (code "107") (name "/~{MD11}") (class "Default")
      (node (ref "E28") (pin "7") (pinfunction "I1_7") (pintype "input"))
      (node (ref "E29") (pin "6") (pinfunction "I2_6") (pintype "input"))
      (node (ref "U$2") (pin "DP1") (pinfunction "1_DP1") (pintype "bidirectional"))
    )
    (net (code "108") (name "/~{NOT_LAST_XFR}") (class "Default")
      (node (ref "Q1") (pin "1") (pinfunction "E_1") (pintype "passive"))
      (node (ref "U$2") (pin "CM1") (pinfunction "1_CM1") (pintype "bidirectional"))
    )
    (net (code "109") (name "/~{RTM}") (class "Default")
      (node (ref "E13") (pin "7") (pinfunction "D0_7") (pintype "input"))
      (node (ref "E13") (pin "9") (pinfunction "D1_9") (pintype "input"))
      (node (ref "E15") (pin "13") (pinfunction "I_13") (pintype "input"))
      (node (ref "E17") (pin "9") (pinfunction "2Y0_9") (pintype "output"))
      (node (ref "E31") (pin "7") (pinfunction "D0_7") (pintype "input"))
      (node (ref "E31") (pin "9") (pinfunction "D1_9") (pintype "input"))
      (node (ref "E7") (pin "7") (pinfunction "D0_7") (pintype "input"))
      (node (ref "E7") (pin "9") (pinfunction "D1_9") (pintype "input"))
    )
    (net (code "110") (name "/~{SKIP}") (class "Default")
      (node (ref "E22") (pin "4") (pinfunction "O_4") (pintype "open_collector"))
      (node (ref "U$2") (pin "CS1") (pinfunction "1_CS1") (pintype "bidirectional"))
    )
    (net (code "111") (name "/~{SKME}") (class "Default")
      (node (ref "E15") (pin "5") (pinfunction "I_5") (pintype "input"))
      (node (ref "E17") (pin "10") (pinfunction "2Y1_10") (pintype "output"))
    )
    (net (code "112") (name "/~{SKMM}") (class "Default")
      (node (ref "E15") (pin "3") (pinfunction "I_3") (pintype "input"))
      (node (ref "E17") (pin "11") (pinfunction "2Y2_11") (pintype "output"))
    )
    (net (code "113") (name "/~{SMME}") (class "Default")
      (node (ref "E11") (pin "5") (pinfunction "I1_5") (pintype "input"))
      (node (ref "E17") (pin "5") (pinfunction "1Y2_5") (pintype "output"))
    )
    (net (code "114") (name "/~{TP3}") (class "Default")
      (node (ref "E15") (pin "9") (pinfunction "I_9") (pintype "input"))
      (node (ref "E16") (pin "3") (pinfunction "O_3") (pintype "output"))
    )
    (net (code "115") (name "/~{TP4}") (class "Default")
      (node (ref "E12") (pin "9") (pinfunction "I_9") (pintype "input"))
      (node (ref "E25") (pin "12") (pinfunction "I1_12") (pintype "input"))
      (node (ref "E25") (pin "14") (pinfunction "O_14") (pintype "output"))
    )
    (net (code "116") (name "/~{TS2}") (class "Default")
      (node (ref "E6") (pin "3") (pinfunction "CLK_3") (pintype "input"))
      (node (ref "U$2") (pin "CL2") (pinfunction "1_CL2") (pintype "bidirectional"))
    )
    (net (code "117") (name "/~{USER_MODE}") (class "Default")
      (node (ref "E9") (pin "8") (pinfunction "O_8") (pintype "output"))
      (node (ref "U$2") (pin "DM2") (pinfunction "1_DM2") (pintype "bidirectional"))
    )
    (net (code "118") (name "GND") (class "Default")
      (node (ref "C1") (pin "-") (pinfunction "-_-") (pintype "passive"))
      (node (ref "C10") (pin "-") (pinfunction "-_-") (pintype "passive"))
      (node (ref "C11") (pin "-") (pinfunction "-_-") (pintype "passive"))
      (node (ref "C12") (pin "-") (pinfunction "-_-") (pintype "passive"))
      (node (ref "C13") (pin "-") (pinfunction "-_-") (pintype "passive"))
      (node (ref "C14") (pin "-") (pinfunction "-_-") (pintype "passive"))
      (node (ref "C2") (pin "-") (pinfunction "-_-") (pintype "passive"))
      (node (ref "C3") (pin "-") (pinfunction "-_-") (pintype "passive"))
      (node (ref "C4") (pin "-") (pinfunction "-_-") (pintype "passive"))
      (node (ref "C5") (pin "-") (pinfunction "-_-") (pintype "passive"))
      (node (ref "C6") (pin "-") (pinfunction "-_-") (pintype "passive"))
      (node (ref "C7") (pin "-") (pinfunction "-_-") (pintype "passive"))
      (node (ref "C8") (pin "-") (pinfunction "-_-") (pintype "passive"))
      (node (ref "C9") (pin "-") (pinfunction "-_-") (pintype "passive"))
      (node (ref "E10") (pin "10") (pinfunction "I1_10") (pintype "input"))
      (node (ref "E10") (pin "11") (pinfunction "I0_11") (pintype "input"))
      (node (ref "E10") (pin "5") (pinfunction "I1_5") (pintype "input"))
      (node (ref "E10") (pin "6") (pinfunction "I0_6") (pintype "input"))
      (node (ref "E16") (pin "10") (pinfunction "I1_10") (pintype "input"))
      (node (ref "E16") (pin "5") (pinfunction "I1_5") (pintype "input"))
      (node (ref "E16") (pin "6") (pinfunction "I0_6") (pintype "input"))
      (node (ref "E20") (pin "15") (pinfunction "G_15") (pintype "input"))
      (node (ref "E23") (pin "15") (pinfunction "G_15") (pintype "input"))
      (node (ref "E25") (pin "10") (pinfunction "I1_10") (pintype "input"))
      (node (ref "E25") (pin "5") (pinfunction "I1_5") (pintype "input"))
      (node (ref "E25") (pin "6") (pinfunction "I0_6") (pintype "input"))
      (node (ref "E26") (pin "1") (pinfunction "A1_1") (pintype "input"))
      (node (ref "E26") (pin "2") (pinfunction "A0_2") (pintype "input"))
      (node (ref "E28") (pin "10") (pinfunction "I1_10") (pintype "input"))
      (node (ref "E28") (pin "11") (pinfunction "I0_11") (pintype "input"))
      (node (ref "E28") (pin "5") (pinfunction "I1_5") (pintype "input"))
      (node (ref "E28") (pin "6") (pinfunction "I0_6") (pintype "input"))
      (node (ref "E33") (pin "15") (pinfunction "G_15") (pintype "input"))
      (node (ref "E34") (pin "1") (pinfunction "A3_1") (pintype "input"))
      (node (ref "E34") (pin "12") (pinfunction "I0_12") (pintype "input"))
      (node (ref "E34") (pin "20") (pinfunction "B3_20") (pintype "input"))
      (node (ref "E34") (pin "22") (pinfunction "D3_22") (pintype "input"))
      (node (ref "E34") (pin "26") (pinfunction "I3_26") (pintype "input"))
      (node (ref "E34") (pin "29") (pinfunction "CN_29") (pintype "bidirectional"))
      (node (ref "E34") (pin "31") (pinfunction "F3_31") (pintype "bidirectional"))
      (node (ref "E34") (pin "40") (pinfunction "~{OE}_40") (pintype "bidirectional"))
      (node (ref "E34") (pin "5") (pinfunction "I6_5") (pintype "input"))
      (node (ref "E34") (pin "6") (pinfunction "I8_6") (pintype "input"))
      (node (ref "E4") (pin "10") (pinfunction "I1_10") (pintype "input"))
      (node (ref "E4") (pin "11") (pinfunction "I0_11") (pintype "input"))
      (node (ref "E4") (pin "5") (pinfunction "I1_5") (pintype "input"))
      (node (ref "E4") (pin "6") (pinfunction "I0_6") (pintype "input"))
      (node (ref "J1") (pin "1") (pinfunction "1_1") (pintype "passive"))
      (node (ref "J1") (pin "8") (pinfunction "8_8") (pintype "passive"))
      (node (ref "J1") (pin "9") (pinfunction "9_9") (pintype "passive"))
      (node (ref "R9") (pin "2") (pinfunction "2_2") (pintype "passive"))
      (node (ref "U$2") (pin "AC1") (pinfunction "1_AC1") (pintype "bidirectional"))
      (node (ref "U$2") (pin "AC2") (pinfunction "1_AC2") (pintype "bidirectional"))
      (node (ref "U$2") (pin "AF1") (pinfunction "1_AF1") (pintype "bidirectional"))
      (node (ref "U$2") (pin "AF2") (pinfunction "1_AF2") (pintype "bidirectional"))
      (node (ref "U$2") (pin "AN1") (pinfunction "1_AN1") (pintype "bidirectional"))
      (node (ref "U$2") (pin "AN2") (pinfunction "1_AN2") (pintype "bidirectional"))
      (node (ref "U$2") (pin "AT1") (pinfunction "1_AT1") (pintype "bidirectional"))
      (node (ref "U$2") (pin "AT2") (pinfunction "1_AT2") (pintype "bidirectional"))
      (node (ref "U$2") (pin "BC1") (pinfunction "1_BC1") (pintype "bidirectional"))
      (node (ref "U$2") (pin "BC2") (pinfunction "1_BC2") (pintype "bidirectional"))
      (node (ref "U$2") (pin "BF1") (pinfunction "1_BF1") (pintype "bidirectional"))
      (node (ref "U$2") (pin "BF2") (pinfunction "1_BF2") (pintype "bidirectional"))
      (node (ref "U$2") (pin "BN1") (pinfunction "1_BN1") (pintype "bidirectional"))
      (node (ref "U$2") (pin "BN2") (pinfunction "1_BN2") (pintype "bidirectional"))
      (node (ref "U$2") (pin "BT1") (pinfunction "1_BT1") (pintype "bidirectional"))
      (node (ref "U$2") (pin "BT2") (pinfunction "1_BT2") (pintype "bidirectional"))
      (node (ref "U$2") (pin "CC1") (pinfunction "1_CC1") (pintype "bidirectional"))
      (node (ref "U$2") (pin "CC2") (pinfunction "1_CC2") (pintype "bidirectional"))
      (node (ref "U$2") (pin "CN1") (pinfunction "1_CN1") (pintype "bidirectional"))
      (node (ref "U$2") (pin "CN2") (pinfunction "1_CN2") (pintype "bidirectional"))
      (node (ref "U$2") (pin "CT1") (pinfunction "1_CT1") (pintype "bidirectional"))
      (node (ref "U$2") (pin "CT2") (pinfunction "1_CT2") (pintype "bidirectional"))
      (node (ref "U$2") (pin "DC1") (pinfunction "1_DC1") (pintype "bidirectional"))
      (node (ref "U$2") (pin "DC2") (pinfunction "1_DC2") (pintype "bidirectional"))
      (node (ref "U$2") (pin "DF1") (pinfunction "1_DF1") (pintype "bidirectional"))
      (node (ref "U$2") (pin "DF2") (pinfunction "1_DF2") (pintype "bidirectional"))
      (node (ref "U$2") (pin "DT1") (pinfunction "1_DT1") (pintype "bidirectional"))
      (node (ref "U$2") (pin "DT2") (pinfunction "1_DT2") (pintype "bidirectional"))
    )
    (net (code "119") (name "Net-(E1A-I0)") (class "Default")
      (node (ref "E1") (pin "2") (pinfunction "I0_2") (pintype "input"))
      (node (ref "E2") (pin "7") (pinfunction "Q2_7") (pintype "output"))
    )
    (net (code "120") (name "Net-(E1B-I0)") (class "Default")
      (node (ref "E1") (pin "5") (pinfunction "I0_5") (pintype "input"))
      (node (ref "E2") (pin "2") (pinfunction "Q1_2") (pintype "output"))
    )
    (net (code "121") (name "Net-(E1C-I0)") (class "Default")
      (node (ref "C9") (pin "+") (pinfunction "+_+") (pintype "passive"))
      (node (ref "E1") (pin "8") (pinfunction "I0_8") (pintype "input"))
      (node (ref "R3") (pin "1") (pinfunction "1_1") (pintype "passive"))
    )
    (net (code "122") (name "Net-(E1C-I1)") (class "Default")
      (node (ref "E1") (pin "9") (pinfunction "I1_9") (pintype "input"))
      (node (ref "E6") (pin "5") (pinfunction "Q_5") (pintype "output"))
      (node (ref "E9") (pin "1") (pinfunction "I0_1") (pintype "input"))
      (node (ref "E9") (pin "2") (pinfunction "I1_2") (pintype "input"))
      (node (ref "E9") (pin "4") (pinfunction "I2_4") (pintype "input"))
      (node (ref "E9") (pin "5") (pinfunction "I3_5") (pintype "input"))
    )
    (net (code "123") (name "Net-(E1D-I1)") (class "Default")
      (node (ref "E1") (pin "12") (pinfunction "I1_12") (pintype "input"))
      (node (ref "E2") (pin "10") (pinfunction "Q3_10") (pintype "output"))
    )
    (net (code "124") (name "Net-(E2A-D1)") (class "Default")
      (node (ref "E2") (pin "4") (pinfunction "D1_4") (pintype "input"))
      (node (ref "E34") (pin "36") (pinfunction "Y0_36") (pintype "output"))
    )
    (net (code "125") (name "Net-(E2A-D2)") (class "Default")
      (node (ref "E2") (pin "5") (pinfunction "D2_5") (pintype "input"))
      (node (ref "E34") (pin "37") (pinfunction "Y1_37") (pintype "output"))
    )
    (net (code "126") (name "Net-(E2A-D3)") (class "Default")
      (node (ref "E2") (pin "12") (pinfunction "D3_12") (pintype "input"))
      (node (ref "E34") (pin "38") (pinfunction "Y2_38") (pintype "output"))
    )
    (net (code "127") (name "Net-(E6A-~{Q})") (class "Default")
      (node (ref "E6") (pin "6") (pinfunction "~{Q}_6") (pintype "output"))
      (node (ref "E9") (pin "12") (pinfunction "I2_12") (pintype "input"))
      (node (ref "E9") (pin "13") (pinfunction "I3_13") (pintype "input"))
    )
    (net (code "128") (name "Net-(E7A-O0)") (class "Default")
      (node (ref "E7") (pin "14") (pinfunction "O0_14") (pintype "input"))
      (node (ref "E8") (pin "10") (pinfunction "Q3_10") (pintype "output"))
    )
    (net (code "129") (name "Net-(E7A-O1)") (class "Default")
      (node (ref "E7") (pin "11") (pinfunction "O1_11") (pintype "input"))
      (node (ref "E8") (pin "15") (pinfunction "Q4_15") (pintype "output"))
    )
    (net (code "130") (name "Net-(E7A-O2)") (class "Default")
      (node (ref "E7") (pin "2") (pinfunction "O2_2") (pintype "input"))
      (node (ref "E8") (pin "7") (pinfunction "Q2_7") (pintype "output"))
    )
    (net (code "131") (name "Net-(E7A-O3)") (class "Default")
      (node (ref "E7") (pin "5") (pinfunction "O3_5") (pintype "input"))
      (node (ref "E8") (pin "2") (pinfunction "Q1_2") (pintype "output"))
    )
    (net (code "132") (name "Net-(E9C-O)") (class "Default")
      (node (ref "E9") (pin "6") (pinfunction "O_6") (pintype "output"))
      (node (ref "R3") (pin "2") (pinfunction "2_2") (pintype "passive"))
    )
    (net (code "133") (name "Net-(E11A-I1)") (class "Default")
      (node (ref "C11") (pin "+") (pinfunction "+_+") (pintype "passive"))
      (node (ref "E11") (pin "2") (pinfunction "I1_2") (pintype "input"))
      (node (ref "R5") (pin "1") (pinfunction "1_1") (pintype "passive"))
    )
    (net (code "134") (name "Net-(E11A-O)") (class "Default")
      (node (ref "E11") (pin "3") (pinfunction "O_3") (pintype "output"))
      (node (ref "E26") (pin "12") (pinfunction "WE_12") (pintype "input"))
    )
    (net (code "135") (name "Net-(E11C-O)") (class "Default")
      (node (ref "E11") (pin "8") (pinfunction "O_8") (pintype "output"))
      (node (ref "E12") (pin "11") (pinfunction "I_11") (pintype "input"))
      (node (ref "E21") (pin "9") (pinfunction "I0_9") (pintype "input"))
      (node (ref "E30") (pin "4") (pinfunction "I0_4") (pintype "input"))
    )
    (net (code "136") (name "Net-(E11D-I0)") (class "Default")
      (node (ref "C10") (pin "+") (pinfunction "+_+") (pintype "passive"))
      (node (ref "E11") (pin "12") (pinfunction "I0_12") (pintype "input"))
      (node (ref "R4") (pin "1") (pinfunction "1_1") (pintype "passive"))
    )
    (net (code "137") (name "Net-(E11D-O)") (class "Default")
      (node (ref "E11") (pin "11") (pinfunction "O_11") (pintype "output"))
      (node (ref "E34") (pin "15") (pinfunction "CP_15") (pintype "input"))
    )
    (net (code "138") (name "Net-(E12A-O)") (class "Default")
      (node (ref "E12") (pin "2") (pinfunction "O_2") (pintype "output"))
      (node (ref "E18") (pin "14") (pinfunction "2G_14") (pintype "input"))
      (node (ref "E18") (pin "2") (pinfunction "1G_2") (pintype "input"))
    )
    (net (code "139") (name "Net-(E12C-O)") (class "Default")
      (node (ref "E12") (pin "6") (pinfunction "O_6") (pintype "output"))
      (node (ref "E30") (pin "9") (pinfunction "I3_9") (pintype "input"))
    )
    (net (code "140") (name "Net-(E13A-O0)") (class "Default")
      (node (ref "E13") (pin "14") (pinfunction "O0_14") (pintype "input"))
      (node (ref "E14") (pin "10") (pinfunction "Q3_10") (pintype "output"))
    )
    (net (code "141") (name "Net-(E13A-O1)") (class "Default")
      (node (ref "E13") (pin "11") (pinfunction "O1_11") (pintype "input"))
      (node (ref "E14") (pin "15") (pinfunction "Q4_15") (pintype "output"))
    )
    (net (code "142") (name "Net-(E13A-O2)") (class "Default")
      (node (ref "E13") (pin "2") (pinfunction "O2_2") (pintype "input"))
      (node (ref "E14") (pin "7") (pinfunction "Q2_7") (pintype "output"))
    )
    (net (code "143") (name "Net-(E13A-O3)") (class "Default")
      (node (ref "E13") (pin "5") (pinfunction "O3_5") (pintype "input"))
      (node (ref "E14") (pin "2") (pinfunction "Q1_2") (pintype "output"))
    )
    (net (code "144") (name "Net-(E15B-O)") (class "Default")
      (node (ref "E15") (pin "4") (pinfunction "O_4") (pintype "output"))
      (node (ref "E22") (pin "11") (pinfunction "I0_11") (pintype "input"))
      (node (ref "E22") (pin "12") (pinfunction "I1_12") (pintype "input"))
    )
    (net (code "145") (name "Net-(E15F-O)") (class "Default")
      (node (ref "E15") (pin "12") (pinfunction "O_12") (pintype "output"))
      (node (ref "E19") (pin "2") (pinfunction "I0_2") (pintype "input"))
      (node (ref "E19") (pin "3") (pinfunction "I1_3") (pintype "input"))
      (node (ref "E19") (pin "5") (pinfunction "I0_5") (pintype "input"))
      (node (ref "E19") (pin "6") (pinfunction "I1_6") (pintype "input"))
    )
    (net (code "146") (name "Net-(E20A-2Y)") (class "Default")
      (node (ref "E20") (pin "7") (pinfunction "2Y_7") (pintype "tri_state"))
      (node (ref "E26") (pin "7") (pinfunction "A4_7") (pintype "input"))
    )
    (net (code "147") (name "Net-(E20A-3Y)") (class "Default")
      (node (ref "E20") (pin "9") (pinfunction "3Y_9") (pintype "tri_state"))
      (node (ref "E26") (pin "14") (pinfunction "A3_14") (pintype "input"))
    )
    (net (code "148") (name "Net-(E20A-4Y)") (class "Default")
      (node (ref "E20") (pin "12") (pinfunction "4Y_12") (pintype "tri_state"))
      (node (ref "E26") (pin "15") (pinfunction "A2_15") (pintype "input"))
    )
    (net (code "149") (name "Net-(E21A-O)") (class "Default")
      (node (ref "E21") (pin "3") (pinfunction "O_3") (pintype "output"))
      (node (ref "E27") (pin "9") (pinfunction "CLK_9") (pintype "input"))
    )
    (net (code "150") (name "Net-(E21B-O)") (class "Default")
      (node (ref "E21") (pin "6") (pinfunction "O_6") (pintype "output"))
      (node (ref "E6") (pin "1") (pinfunction "CLR_1") (pintype "input"))
    )
    (net (code "151") (name "Net-(E21C-I1)") (class "Default")
      (node (ref "E21") (pin "10") (pinfunction "I1_10") (pintype "input"))
      (node (ref "E22") (pin "1") (pinfunction "O_1") (pintype "open_collector"))
      (node (ref "R8") (pin "2") (pinfunction "2_2") (pintype "passive"))
    )
    (net (code "152") (name "Net-(E23A-2Y)") (class "Default")
      (node (ref "E23") (pin "7") (pinfunction "2Y_7") (pintype "tri_state"))
      (node (ref "E26") (pin "11") (pinfunction "A7_11") (pintype "input"))
    )
    (net (code "153") (name "Net-(E23A-3Y)") (class "Default")
      (node (ref "E23") (pin "9") (pinfunction "3Y_9") (pintype "tri_state"))
      (node (ref "E26") (pin "10") (pinfunction "A6_10") (pintype "input"))
    )
    (net (code "154") (name "Net-(E23A-4Y)") (class "Default")
      (node (ref "E23") (pin "12") (pinfunction "4Y_12") (pintype "tri_state"))
      (node (ref "E26") (pin "9") (pinfunction "A5_9") (pintype "input"))
    )
    (net (code "155") (name "Net-(E24B-I0)") (class "Default")
      (node (ref "E24") (pin "3") (pinfunction "I0_3") (pintype "input"))
      (node (ref "E26") (pin "6") (pinfunction "DOUT_6") (pintype "open_collector"))
      (node (ref "R10") (pin "2") (pinfunction "2_2") (pintype "passive"))
    )
    (net (code "156") (name "Net-(E27A-Q1)") (class "Default")
      (node (ref "E27") (pin "2") (pinfunction "Q1_2") (pintype "output"))
      (node (ref "E33") (pin "2") (pinfunction "1A_2") (pintype "input"))
    )
    (net (code "157") (name "Net-(E27A-Q2)") (class "Default")
      (node (ref "E27") (pin "7") (pinfunction "Q2_7") (pintype "output"))
      (node (ref "E33") (pin "5") (pinfunction "2A_5") (pintype "input"))
    )
    (net (code "158") (name "Net-(E27A-Q4)") (class "Default")
      (node (ref "E27") (pin "15") (pinfunction "Q4_15") (pintype "output"))
      (node (ref "E33") (pin "14") (pinfunction "4A_14") (pintype "input"))
    )
    (net (code "159") (name "Net-(E31A-O0)") (class "Default")
      (node (ref "E31") (pin "14") (pinfunction "O0_14") (pintype "input"))
      (node (ref "E32") (pin "10") (pinfunction "Q3_10") (pintype "output"))
    )
    (net (code "160") (name "Net-(E31A-O1)") (class "Default")
      (node (ref "E31") (pin "11") (pinfunction "O1_11") (pintype "input"))
      (node (ref "E32") (pin "15") (pinfunction "Q4_15") (pintype "output"))
    )
    (net (code "161") (name "Net-(E31A-O2)") (class "Default")
      (node (ref "E31") (pin "2") (pinfunction "O2_2") (pintype "input"))
      (node (ref "E32") (pin "7") (pinfunction "Q2_7") (pintype "output"))
    )
    (net (code "162") (name "Net-(E31A-O3)") (class "Default")
      (node (ref "E31") (pin "5") (pinfunction "O3_5") (pintype "input"))
      (node (ref "E32") (pin "2") (pinfunction "Q1_2") (pintype "output"))
    )
    (net (code "163") (name "Net-(E33A-1Y)") (class "Default")
      (node (ref "E33") (pin "4") (pinfunction "1Y_4") (pintype "tri_state"))
      (node (ref "E34") (pin "3") (pinfunction "A1_3") (pintype "input"))
    )
    (net (code "164") (name "Net-(E33A-2Y)") (class "Default")
      (node (ref "E33") (pin "7") (pinfunction "2Y_7") (pintype "tri_state"))
      (node (ref "E34") (pin "4") (pinfunction "A0_4") (pintype "input"))
    )
    (net (code "165") (name "Net-(E33A-4Y)") (class "Default")
      (node (ref "E33") (pin "12") (pinfunction "4Y_12") (pintype "tri_state"))
      (node (ref "E34") (pin "2") (pinfunction "A2_2") (pintype "input"))
    )
    (net (code "166") (name "Net-(E34A-Q0)") (class "Default")
      (node (ref "E34") (pin "16") (pinfunction "Q3_16") (pintype "bidirectional"))
      (node (ref "E34") (pin "21") (pinfunction "Q0_21") (pintype "bidirectional"))
      (node (ref "E34") (pin "8") (pinfunction "RAM3_8") (pintype "bidirectional"))
      (node (ref "E34") (pin "9") (pinfunction "RAM0_9") (pintype "bidirectional"))
      (node (ref "R2") (pin "1") (pinfunction "1_1") (pintype "passive"))
    )
    (net (code "167") (name "Net-(Q1-C)") (class "Default")
      (node (ref "Q1") (pin "3") (pinfunction "C_3") (pintype "passive"))
      (node (ref "R7") (pin "2") (pinfunction "2_2") (pintype "passive"))
    )
    (net (code "168") (name "VCC") (class "Default")
      (node (ref "C1") (pin "+") (pinfunction "+_+") (pintype "passive"))
      (node (ref "C12") (pin "+") (pinfunction "+_+") (pintype "passive"))
      (node (ref "C13") (pin "+") (pinfunction "+_+") (pintype "passive"))
      (node (ref "C14") (pin "+") (pinfunction "+_+") (pintype "passive"))
      (node (ref "C2") (pin "+") (pinfunction "+_+") (pintype "passive"))
      (node (ref "C3") (pin "+") (pinfunction "+_+") (pintype "passive"))
      (node (ref "C4") (pin "+") (pinfunction "+_+") (pintype "passive"))
      (node (ref "C5") (pin "+") (pinfunction "+_+") (pintype "passive"))
      (node (ref "C6") (pin "+") (pinfunction "+_+") (pintype "passive"))
      (node (ref "C7") (pin "+") (pinfunction "+_+") (pintype "passive"))
      (node (ref "C8") (pin "+") (pinfunction "+_+") (pintype "passive"))
      (node (ref "E14") (pin "1") (pinfunction "CLR_1") (pintype "input"))
      (node (ref "E32") (pin "1") (pinfunction "CLR_1") (pintype "input"))
      (node (ref "E34") (pin "14") (pinfunction "I2_14") (pintype "input"))
      (node (ref "E34") (pin "27") (pinfunction "I5_27") (pintype "input"))
      (node (ref "E34") (pin "28") (pinfunction "I4_28") (pintype "input"))
      (node (ref "E34") (pin "7") (pinfunction "I7_7") (pintype "input"))
      (node (ref "E6") (pin "10") (pinfunction "PRE_10") (pintype "input"))
      (node (ref "E6") (pin "4") (pinfunction "PRE_4") (pintype "input"))
      (node (ref "R1") (pin "2") (pinfunction "2_2") (pintype "passive"))
      (node (ref "R10") (pin "1") (pinfunction "1_1") (pintype "passive"))
      (node (ref "R2") (pin "2") (pinfunction "2_2") (pintype "passive"))
      (node (ref "R6") (pin "1") (pinfunction "1_1") (pintype "passive"))
      (node (ref "R7") (pin "1") (pinfunction "1_1") (pintype "passive"))
      (node (ref "R8") (pin "1") (pinfunction "1_1") (pintype "passive"))
      (node (ref "U$2") (pin "AA2") (pinfunction "1_AA2") (pintype "bidirectional"))
      (node (ref "U$2") (pin "BA2") (pinfunction "1_BA2") (pintype "bidirectional"))
      (node (ref "U$2") (pin "CA2") (pinfunction "1_CA2") (pintype "bidirectional"))
    )
    (net (code "169") (name "unconnected-(E2A-~{Q1}-Pad3)") (class "Default")
      (node (ref "E2") (pin "3") (pinfunction "~{Q1}_3") (pintype "output"))
    )
    (net (code "170") (name "unconnected-(E2A-~{Q2}-Pad6)") (class "Default")
      (node (ref "E2") (pin "6") (pinfunction "~{Q2}_6") (pintype "output"))
    )
    (net (code "171") (name "unconnected-(E2A-~{Q3}-Pad11)") (class "Default")
      (node (ref "E2") (pin "11") (pinfunction "~{Q3}_11") (pintype "output"))
    )
    (net (code "172") (name "unconnected-(E2A-~{Q4}-Pad14)") (class "Default")
      (node (ref "E2") (pin "14") (pinfunction "~{Q4}_14") (pintype "output"))
    )
    (net (code "173") (name "unconnected-(E3A-~{Q}-Pad6)") (class "Default")
      (node (ref "E3") (pin "6") (pinfunction "~{Q}_6") (pintype "output"))
    )
    (net (code "174") (name "unconnected-(E3B-Q-Pad9)") (class "Default")
      (node (ref "E3") (pin "9") (pinfunction "Q_9") (pintype "output"))
    )
    (net (code "175") (name "unconnected-(E6B-~{Q}-Pad8)") (class "Default")
      (node (ref "E6") (pin "8") (pinfunction "~{Q}_8") (pintype "output"))
    )
    (net (code "176") (name "unconnected-(E8A-CLR-Pad1)") (class "Default")
      (node (ref "E8") (pin "1") (pinfunction "CLR_1") (pintype "input"))
    )
    (net (code "177") (name "unconnected-(E8A-~{Q1}-Pad3)") (class "Default")
      (node (ref "E8") (pin "3") (pinfunction "~{Q1}_3") (pintype "output"))
    )
    (net (code "178") (name "unconnected-(E8A-~{Q2}-Pad6)") (class "Default")
      (node (ref "E8") (pin "6") (pinfunction "~{Q2}_6") (pintype "output"))
    )
    (net (code "179") (name "unconnected-(E8A-~{Q3}-Pad11)") (class "Default")
      (node (ref "E8") (pin "11") (pinfunction "~{Q3}_11") (pintype "output"))
    )
    (net (code "180") (name "unconnected-(E8A-~{Q4}-Pad14)") (class "Default")
      (node (ref "E8") (pin "14") (pinfunction "~{Q4}_14") (pintype "output"))
    )
    (net (code "181") (name "unconnected-(E14A-~{Q1}-Pad3)") (class "Default")
      (node (ref "E14") (pin "3") (pinfunction "~{Q1}_3") (pintype "output"))
    )
    (net (code "182") (name "unconnected-(E14A-~{Q2}-Pad6)") (class "Default")
      (node (ref "E14") (pin "6") (pinfunction "~{Q2}_6") (pintype "output"))
    )
    (net (code "183") (name "unconnected-(E14A-~{Q3}-Pad11)") (class "Default")
      (node (ref "E14") (pin "11") (pinfunction "~{Q3}_11") (pintype "output"))
    )
    (net (code "184") (name "unconnected-(E14A-~{Q4}-Pad14)") (class "Default")
      (node (ref "E14") (pin "14") (pinfunction "~{Q4}_14") (pintype "output"))
    )
    (net (code "185") (name "unconnected-(E17A-1Y1-Pad6)") (class "Default")
      (node (ref "E17") (pin "6") (pinfunction "1Y1_6") (pintype "output"))
    )
    (net (code "186") (name "unconnected-(E18A-1Y0-Pad7)") (class "Default")
      (node (ref "E18") (pin "7") (pinfunction "1Y0_7") (pintype "output"))
    )
    (net (code "187") (name "unconnected-(E18A-1Y1-Pad6)") (class "Default")
      (node (ref "E18") (pin "6") (pinfunction "1Y1_6") (pintype "output"))
    )
    (net (code "188") (name "unconnected-(E18A-1Y2-Pad5)") (class "Default")
      (node (ref "E18") (pin "5") (pinfunction "1Y2_5") (pintype "output"))
    )
    (net (code "189") (name "unconnected-(E18A-1Y3-Pad4)") (class "Default")
      (node (ref "E18") (pin "4") (pinfunction "1Y3_4") (pintype "output"))
    )
    (net (code "190") (name "unconnected-(E18A-2Y0-Pad9)") (class "Default")
      (node (ref "E18") (pin "9") (pinfunction "2Y0_9") (pintype "output"))
    )
    (net (code "191") (name "unconnected-(E18A-2Y3-Pad12)") (class "Default")
      (node (ref "E18") (pin "12") (pinfunction "2Y3_12") (pintype "output"))
    )
    (net (code "192") (name "unconnected-(E20A-1A-Pad2)") (class "Default")
      (node (ref "E20") (pin "2") (pinfunction "1A_2") (pintype "input"))
    )
    (net (code "193") (name "unconnected-(E20A-1B-Pad3)") (class "Default")
      (node (ref "E20") (pin "3") (pinfunction "1B_3") (pintype "input"))
    )
    (net (code "194") (name "unconnected-(E20A-1Y-Pad4)") (class "Default")
      (node (ref "E20") (pin "4") (pinfunction "1Y_4") (pintype "tri_state"))
    )
    (net (code "195") (name "unconnected-(E23A-1A-Pad2)") (class "Default")
      (node (ref "E23") (pin "2") (pinfunction "1A_2") (pintype "input"))
    )
    (net (code "196") (name "unconnected-(E23A-1B-Pad3)") (class "Default")
      (node (ref "E23") (pin "3") (pinfunction "1B_3") (pintype "input"))
    )
    (net (code "197") (name "unconnected-(E23A-1Y-Pad4)") (class "Default")
      (node (ref "E23") (pin "4") (pinfunction "1Y_4") (pintype "tri_state"))
    )
    (net (code "198") (name "unconnected-(E27A-~{Q1}-Pad3)") (class "Default")
      (node (ref "E27") (pin "3") (pinfunction "~{Q1}_3") (pintype "output"))
    )
    (net (code "199") (name "unconnected-(E27A-~{Q2}-Pad6)") (class "Default")
      (node (ref "E27") (pin "6") (pinfunction "~{Q2}_6") (pintype "output"))
    )
    (net (code "200") (name "unconnected-(E27A-~{Q3}-Pad11)") (class "Default")
      (node (ref "E27") (pin "11") (pinfunction "~{Q3}_11") (pintype "output"))
    )
    (net (code "201") (name "unconnected-(E27A-~{Q4}-Pad14)") (class "Default")
      (node (ref "E27") (pin "14") (pinfunction "~{Q4}_14") (pintype "output"))
    )
    (net (code "202") (name "unconnected-(E32A-~{Q1}-Pad3)") (class "Default")
      (node (ref "E32") (pin "3") (pinfunction "~{Q1}_3") (pintype "output"))
    )
    (net (code "203") (name "unconnected-(E32A-~{Q2}-Pad6)") (class "Default")
      (node (ref "E32") (pin "6") (pinfunction "~{Q2}_6") (pintype "output"))
    )
    (net (code "204") (name "unconnected-(E32A-~{Q3}-Pad11)") (class "Default")
      (node (ref "E32") (pin "11") (pinfunction "~{Q3}_11") (pintype "output"))
    )
    (net (code "205") (name "unconnected-(E32A-~{Q4}-Pad14)") (class "Default")
      (node (ref "E32") (pin "14") (pinfunction "~{Q4}_14") (pintype "output"))
    )
    (net (code "206") (name "unconnected-(E33A-3A-Pad11)") (class "Default")
      (node (ref "E33") (pin "11") (pinfunction "3A_11") (pintype "input"))
    )
    (net (code "207") (name "unconnected-(E33A-3B-Pad10)") (class "Default")
      (node (ref "E33") (pin "10") (pinfunction "3B_10") (pintype "input"))
    )
    (net (code "208") (name "unconnected-(E33A-3Y-Pad9)") (class "Default")
      (node (ref "E33") (pin "9") (pinfunction "3Y_9") (pintype "tri_state"))
    )
    (net (code "209") (name "unconnected-(E34A-CN+4-Pad33)") (class "Default")
      (node (ref "E34") (pin "33") (pinfunction "CN+4_33") (pintype "output"))
    )
    (net (code "210") (name "unconnected-(E34A-F=0-Pad11)") (class "Default")
      (node (ref "E34") (pin "11") (pinfunction "F=0_11") (pintype "output"))
    )
    (net (code "211") (name "unconnected-(E34A-OVR-Pad34)") (class "Default")
      (node (ref "E34") (pin "34") (pinfunction "OVR_34") (pintype "output"))
    )
    (net (code "212") (name "unconnected-(E34A-Y3-Pad39)") (class "Default")
      (node (ref "E34") (pin "39") (pinfunction "Y3_39") (pintype "output"))
    )
    (net (code "213") (name "unconnected-(E34A-~{G}-Pad32)") (class "Default")
      (node (ref "E34") (pin "32") (pinfunction "~{G}_32") (pintype "output"))
    )
    (net (code "214") (name "unconnected-(E34A-~{P}-Pad35)") (class "Default")
      (node (ref "E34") (pin "35") (pinfunction "~{P}_35") (pintype "output"))
    )
  )
)
